# sb3.net
KiCad netlist of a schematic drawn in EAGLE
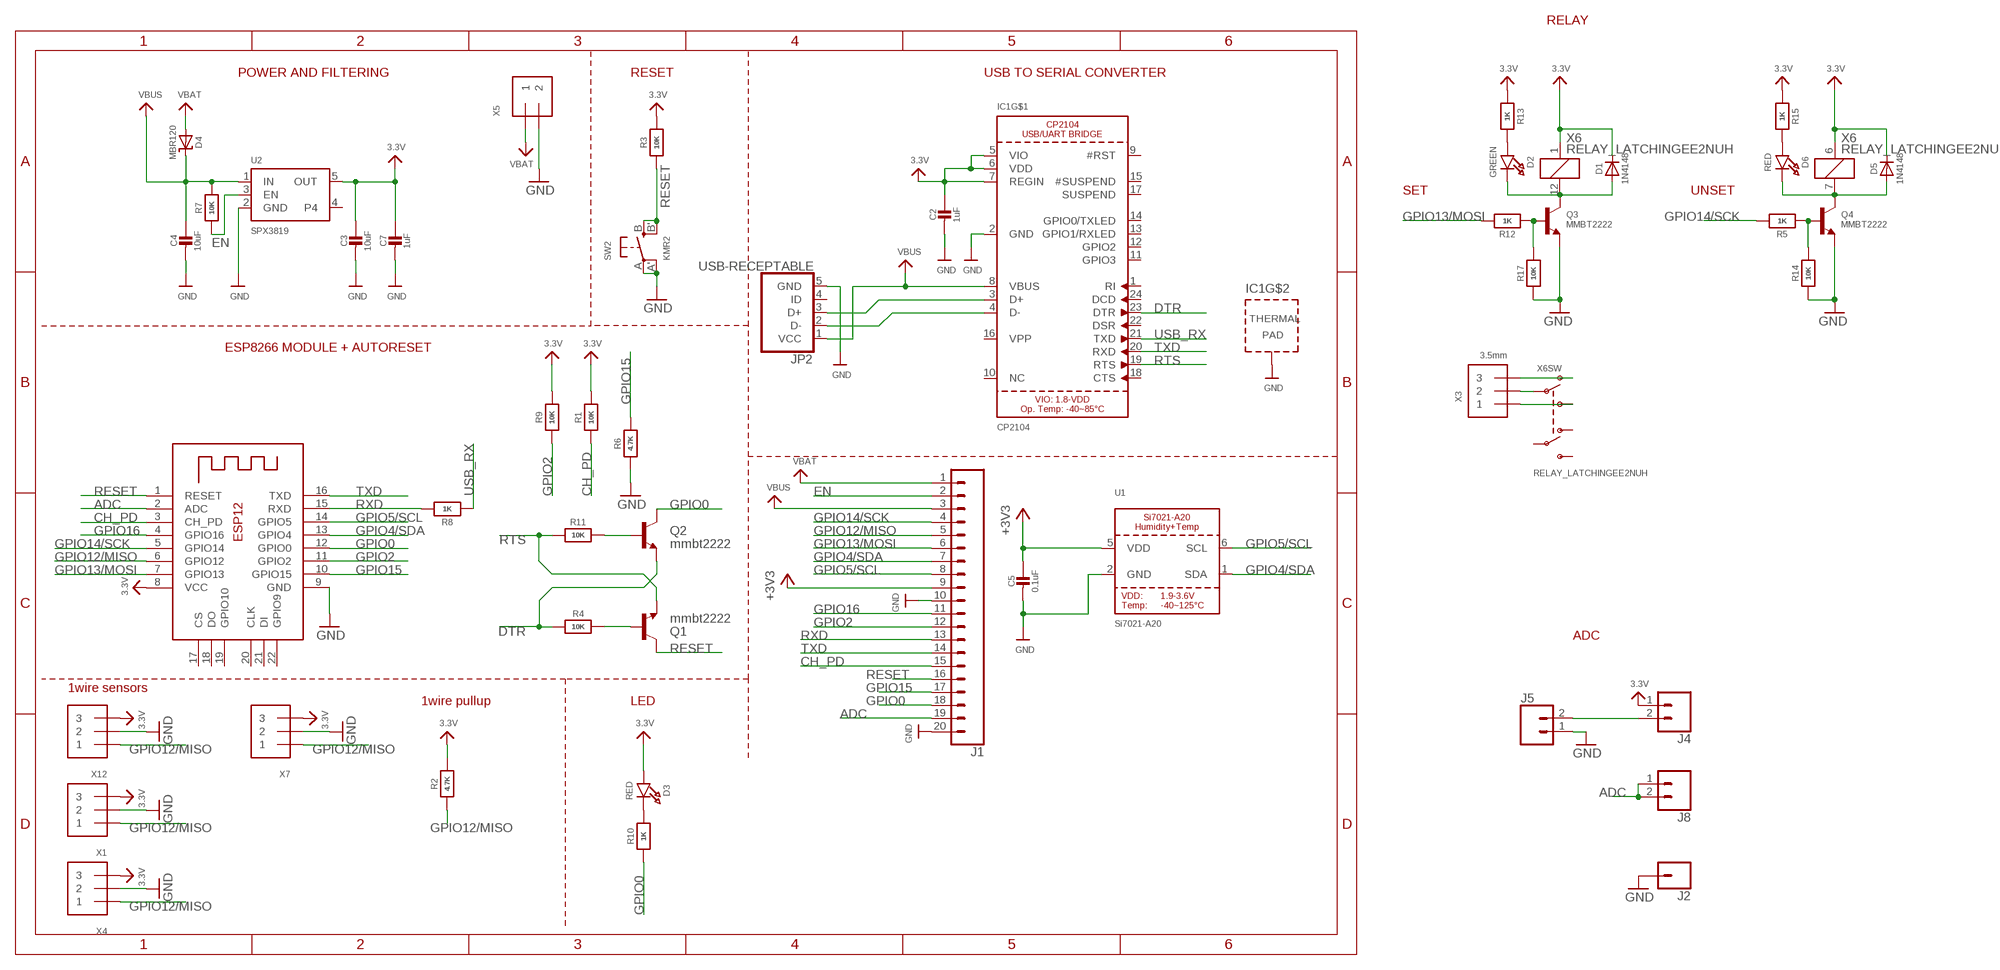
[diagram p0: schematic, sheet 1]

(export (version "E")
  (design (tool "Eeschema 10.0.6"))
  (components
    (comp (ref "C2")
      (value "1uF")
      (footprint "eagle-import:0603-NO")
      (libsource (lib "eagle-import") (part "CAP_CERAMIC0603_NO"))
    )
    (comp (ref "C3")
      (value "10uF")
      (footprint "eagle-import:0603-NO")
      (libsource (lib "eagle-import") (part "CAP_CERAMIC0603_NO"))
    )
    (comp (ref "C4")
      (value "10uF")
      (footprint "eagle-import:0603-NO")
      (libsource (lib "eagle-import") (part "CAP_CERAMIC0603_NO"))
    )
    (comp (ref "C5")
      (value "0.1uF")
      (footprint "eagle-import:0603-NO")
      (libsource (lib "eagle-import") (part "CAP_CERAMIC0603_NO"))
    )
    (comp (ref "C7")
      (value "1uF")
      (footprint "eagle-import:0603-NO")
      (libsource (lib "eagle-import") (part "CAP_CERAMIC0603_NO"))
    )
    (comp (ref "D1")
      (value "1N4148")
      (footprint "eagle-import:SOD-323")
      (libsource (lib "eagle-import") (part "DIODESOD-323"))
    )
    (comp (ref "D2")
      (value "GREEN")
      (footprint "eagle-import:CHIPLED_0805_NOOUTLINE")
      (libsource (lib "eagle-import") (part "LED0805_NOOUTLINE"))
    )
    (comp (ref "D3")
      (value "RED")
      (footprint "eagle-import:CHIPLED_0805_NOOUTLINE")
      (libsource (lib "eagle-import") (part "LED0805_NOOUTLINE"))
    )
    (comp (ref "D4")
      (value "MBR120")
      (footprint "eagle-import:SOD-123")
      (libsource (lib "eagle-import") (part "DIODE-SCHOTTKYSOD-123"))
    )
    (comp (ref "D5")
      (value "1N4148")
      (footprint "eagle-import:SOD-323")
      (libsource (lib "eagle-import") (part "DIODESOD-323"))
    )
    (comp (ref "D6")
      (value "RED")
      (footprint "eagle-import:CHIPLED_0805_NOOUTLINE")
      (libsource (lib "eagle-import") (part "LED0805_NOOUTLINE"))
    )
    (comp (ref "IC1")
      (value "CP2104")
      (footprint "eagle-import:QFN24_4MM_SMSC")
      (libsource (lib "eagle-import") (part "CP2104"))
    )
    (comp (ref "J1")
      (value "CONN_20")
      (footprint "eagle-import:1X20")
      (libsource (lib "eagle-import") (part "CONN_20"))
    )
    (comp (ref "J2")
      (value "CONN_01")
      (footprint "eagle-import:1X01")
      (libsource (lib "eagle-import") (part "CONN_01"))
    )
    (comp (ref "J4")
      (value "CONN_02")
      (footprint "eagle-import:1X02")
      (libsource (lib "eagle-import") (part "CONN_02"))
    )
    (comp (ref "J5")
      (value "CONN_023.5MM")
      (footprint "eagle-import:SCREWTERMINAL-3.5MM-2")
      (libsource (lib "eagle-import") (part "CONN_023.5MM"))
    )
    (comp (ref "J8")
      (value "CONN_02")
      (footprint "eagle-import:1X02")
      (libsource (lib "eagle-import") (part "CONN_02"))
    )
    (comp (ref "JP2")
      (value "USB-RECEPTABLE")
      (footprint "eagle-import:FCI-10103594-0001LF")
      (libsource (lib "eagle-import") (part "USB-RECEPTABLE"))
    )
    (comp (ref "Q1")
      (value "mmbt2222")
      (footprint "eagle-import:SOT23-3")
      (libsource (lib "eagle-import") (part "TRANSISTOR_NPNSOT23-3"))
    )
    (comp (ref "Q2")
      (value "mmbt2222")
      (footprint "eagle-import:SOT23-3")
      (libsource (lib "eagle-import") (part "TRANSISTOR_NPNSOT23-3"))
    )
    (comp (ref "Q3")
      (value "MMBT2222")
      (footprint "eagle-import:SOT23-R")
      (libsource (lib "eagle-import") (part "TRANSISTOR_NPN"))
    )
    (comp (ref "Q4")
      (value "MMBT2222")
      (footprint "eagle-import:SOT23-R")
      (libsource (lib "eagle-import") (part "TRANSISTOR_NPN"))
    )
    (comp (ref "R1")
      (value "10K")
      (footprint "eagle-import:0603-NO")
      (libsource (lib "eagle-import") (part "RESISTOR_0603_NOOUT"))
    )
    (comp (ref "R2")
      (value "4.7K")
      (footprint "eagle-import:0603-NO")
      (libsource (lib "eagle-import") (part "RESISTOR_0603_NOOUT"))
    )
    (comp (ref "R3")
      (value "10K")
      (footprint "eagle-import:0603-NO")
      (libsource (lib "eagle-import") (part "RESISTOR_0603_NOOUT"))
    )
    (comp (ref "R4")
      (value "10K")
      (footprint "eagle-import:0603-NO")
      (libsource (lib "eagle-import") (part "RESISTOR_0603_NOOUT"))
    )
    (comp (ref "R5")
      (value "1K")
      (footprint "eagle-import:0603-NO")
      (libsource (lib "eagle-import") (part "RESISTOR_0603_NOOUT"))
    )
    (comp (ref "R6")
      (value "4.7K")
      (footprint "eagle-import:0603-NO")
      (libsource (lib "eagle-import") (part "RESISTOR_0603_NOOUT"))
    )
    (comp (ref "R7")
      (value "10K")
      (footprint "eagle-import:0603-NO")
      (libsource (lib "eagle-import") (part "RESISTOR_0603_NOOUT"))
    )
    (comp (ref "R8")
      (value "1K")
      (footprint "eagle-import:0603-NO")
      (libsource (lib "eagle-import") (part "RESISTOR_0603_NOOUT"))
    )
    (comp (ref "R9")
      (value "10K")
      (footprint "eagle-import:0603-NO")
      (libsource (lib "eagle-import") (part "RESISTOR_0603_NOOUT"))
    )
    (comp (ref "R10")
      (value "1K")
      (footprint "eagle-import:0603-NO")
      (libsource (lib "eagle-import") (part "RESISTOR_0603_NOOUT"))
    )
    (comp (ref "R11")
      (value "10K")
      (footprint "eagle-import:0603-NO")
      (libsource (lib "eagle-import") (part "RESISTOR_0603_NOOUT"))
    )
    (comp (ref "R12")
      (value "1K")
      (footprint "eagle-import:0603-NO")
      (libsource (lib "eagle-import") (part "RESISTOR_0603_NOOUT"))
    )
    (comp (ref "R13")
      (value "1K")
      (footprint "eagle-import:0603-NO")
      (libsource (lib "eagle-import") (part "RESISTOR_0603_NOOUT"))
    )
    (comp (ref "R14")
      (value "10K")
      (footprint "eagle-import:0603-NO")
      (libsource (lib "eagle-import") (part "RESISTOR_0603_NOOUT"))
    )
    (comp (ref "R15")
      (value "1K")
      (footprint "eagle-import:0603-NO")
      (libsource (lib "eagle-import") (part "RESISTOR_0603_NOOUT"))
    )
    (comp (ref "R17")
      (value "10K")
      (footprint "eagle-import:0603-NO")
      (libsource (lib "eagle-import") (part "RESISTOR_0603_NOOUT"))
    )
    (comp (ref "SW2")
      (value "KMR2")
      (footprint "eagle-import:BTN_KMR2_4.6X2.8")
      (libsource (lib "eagle-import") (part "SWITCH_TACT_SMT4.6X2.8"))
    )
    (comp (ref "U1")
      (value "Si7021-A20")
      (footprint "eagle-import:DFN6_3X3_SI")
      (libsource (lib "eagle-import") (part "SI7021-A20"))
    )
    (comp (ref "U2")
      (value "SPX3819")
      (footprint "eagle-import:SOT23-5")
      (libsource (lib "eagle-import") (part "VREG_SOT23-5"))
    )
    (comp (ref "X1")
      (value "TERMBLOCK_1X3")
      (footprint "eagle-import:TERMBLOCK_1X3-3.5MM")
      (libsource (lib "eagle-import") (part "TERMBLOCK_1X3"))
    )
    (comp (ref "X2")
      (value "ESP-12")
      (footprint "eagle-import:ESP-12E")
      (libsource (lib "eagle-import") (part "ESP-12E"))
    )
    (comp (ref "X3")
      (value "3.5mm")
      (footprint "eagle-import:TERMBLOCK_1X3-3.5MM")
      (libsource (lib "eagle-import") (part "TERMBLOCK_1X3"))
    )
    (comp (ref "X4")
      (value "TERMBLOCK_1X3")
      (footprint "eagle-import:TERMBLOCK_1X3-3.5MM")
      (libsource (lib "eagle-import") (part "TERMBLOCK_1X3"))
    )
    (comp (ref "X5")
      (value "TERMBLOCK_1X2")
      (footprint "eagle-import:TERMBLOCK_1X2-3.5MM")
      (libsource (lib "eagle-import") (part "TERMBLOCK_1X2"))
    )
    (comp (ref "X6")
      (value "RELAY_LATCHINGEE2NUH")
      (footprint "eagle-import:RELAY_EE2_LATCH")
      (libsource (lib "eagle-import") (part "RELAY_LATCHINGEE2NUH"))
    )
    (comp (ref "X7")
      (value "TERMBLOCK_1X3")
      (footprint "eagle-import:TERMBLOCK_1X3-3.5MM")
      (libsource (lib "eagle-import") (part "TERMBLOCK_1X3"))
    )
    (comp (ref "X12")
      (value "TERMBLOCK_1X3")
      (footprint "eagle-import:TERMBLOCK_1X3-3.5MM")
      (libsource (lib "eagle-import") (part "TERMBLOCK_1X3"))
    )
  )
  (nets
    (net (code "1") (name "+3V3") (class "Default")
      (node (ref "C5") (pin "1") (pinfunction "1_1") (pintype "passive"))
      (node (ref "J1") (pin "9") (pinfunction "9_9") (pintype "passive"))
      (node (ref "U1") (pin "5") (pinfunction "VDD_5") (pintype "power_in"))
    )
    (net (code "2") (name "/ADC") (class "Default")
      (node (ref "J1") (pin "19") (pinfunction "19_19") (pintype "passive"))
      (node (ref "J8") (pin "1") (pinfunction "1_1") (pintype "passive"))
      (node (ref "J8") (pin "2") (pinfunction "2_2") (pintype "passive"))
      (node (ref "X2") (pin "2") (pinfunction "ADC_2") (pintype "passive"))
    )
    (net (code "3") (name "/CH_PD") (class "Default")
      (node (ref "J1") (pin "15") (pinfunction "15_15") (pintype "passive"))
      (node (ref "R1") (pin "1") (pinfunction "1_1") (pintype "passive"))
      (node (ref "X2") (pin "3") (pinfunction "CH_PD_3") (pintype "input"))
    )
    (net (code "4") (name "/DTR") (class "Default")
      (node (ref "IC1") (pin "23") (pinfunction "DTR_23") (pintype "output"))
      (node (ref "Q2") (pin "2") (pinfunction "E_2") (pintype "passive"))
      (node (ref "R4") (pin "1") (pinfunction "1_1") (pintype "passive"))
    )
    (net (code "5") (name "/EN") (class "Default")
      (node (ref "J1") (pin "2") (pinfunction "2_2") (pintype "passive"))
      (node (ref "R7") (pin "1") (pinfunction "1_1") (pintype "passive"))
      (node (ref "U2") (pin "3") (pinfunction "EN_3") (pintype "input"))
    )
    (net (code "6") (name "/GPIO0") (class "Default")
      (node (ref "J1") (pin "18") (pinfunction "18_18") (pintype "passive"))
      (node (ref "Q2") (pin "3") (pinfunction "C_3") (pintype "passive"))
      (node (ref "R10") (pin "1") (pinfunction "1_1") (pintype "passive"))
      (node (ref "X2") (pin "12") (pinfunction "GPIO0_12") (pintype "bidirectional"))
    )
    (net (code "7") (name "/GPIO2") (class "Default")
      (node (ref "J1") (pin "12") (pinfunction "12_12") (pintype "passive"))
      (node (ref "R9") (pin "1") (pinfunction "1_1") (pintype "passive"))
      (node (ref "X2") (pin "11") (pinfunction "GPIO2_11") (pintype "bidirectional"))
    )
    (net (code "8") (name "/GPIO4{slash}SDA") (class "Default")
      (node (ref "J1") (pin "7") (pinfunction "7_7") (pintype "passive"))
      (node (ref "U1") (pin "1") (pinfunction "SDA_1") (pintype "open_collector"))
      (node (ref "X2") (pin "13") (pinfunction "GPIO4_13") (pintype "bidirectional"))
    )
    (net (code "9") (name "/GPIO5{slash}SCL") (class "Default")
      (node (ref "J1") (pin "8") (pinfunction "8_8") (pintype "passive"))
      (node (ref "U1") (pin "6") (pinfunction "SCL_6") (pintype "open_collector"))
      (node (ref "X2") (pin "14") (pinfunction "GPIO5_14") (pintype "bidirectional"))
    )
    (net (code "10") (name "/GPIO12{slash}MISO") (class "Default")
      (node (ref "J1") (pin "5") (pinfunction "5_5") (pintype "passive"))
      (node (ref "R2") (pin "1") (pinfunction "1_1") (pintype "passive"))
      (node (ref "X1") (pin "1") (pinfunction "1_1") (pintype "passive"))
      (node (ref "X12") (pin "1") (pinfunction "1_1") (pintype "passive"))
      (node (ref "X2") (pin "6") (pinfunction "GPIO12_6") (pintype "bidirectional"))
      (node (ref "X4") (pin "1") (pinfunction "1_1") (pintype "passive"))
      (node (ref "X7") (pin "1") (pinfunction "1_1") (pintype "passive"))
    )
    (net (code "11") (name "/GPIO13{slash}MOSI") (class "Default")
      (node (ref "J1") (pin "6") (pinfunction "6_6") (pintype "passive"))
      (node (ref "R12") (pin "2") (pinfunction "2_2") (pintype "passive"))
      (node (ref "X2") (pin "7") (pinfunction "GPIO13_7") (pintype "bidirectional"))
    )
    (net (code "12") (name "/GPIO14{slash}SCK") (class "Default")
      (node (ref "J1") (pin "4") (pinfunction "4_4") (pintype "passive"))
      (node (ref "R5") (pin "2") (pinfunction "2_2") (pintype "passive"))
      (node (ref "X2") (pin "5") (pinfunction "GPIO14_5") (pintype "bidirectional"))
    )
    (net (code "13") (name "/GPIO15") (class "Default")
      (node (ref "J1") (pin "17") (pinfunction "17_17") (pintype "passive"))
      (node (ref "R6") (pin "2") (pinfunction "2_2") (pintype "passive"))
      (node (ref "X2") (pin "10") (pinfunction "GPIO15_10") (pintype "bidirectional"))
    )
    (net (code "14") (name "/GPIO16") (class "Default")
      (node (ref "J1") (pin "11") (pinfunction "11_11") (pintype "passive"))
      (node (ref "X2") (pin "4") (pinfunction "GPIO16_4") (pintype "bidirectional"))
    )
    (net (code "15") (name "/RESET") (class "Default")
      (node (ref "J1") (pin "16") (pinfunction "16_16") (pintype "passive"))
      (node (ref "Q1") (pin "3") (pinfunction "C_3") (pintype "passive"))
      (node (ref "R3") (pin "1") (pinfunction "1_1") (pintype "passive"))
      (node (ref "SW2") (pin "B") (pinfunction "S_B") (pintype "passive"))
      (node (ref "SW2") (pin "B'") (pinfunction "S1_B'") (pintype "passive"))
      (node (ref "X2") (pin "1") (pinfunction "RESET_1") (pintype "input"))
    )
    (net (code "16") (name "/RTS") (class "Default")
      (node (ref "IC1") (pin "19") (pinfunction "RTS_19") (pintype "output"))
      (node (ref "Q1") (pin "2") (pinfunction "E_2") (pintype "passive"))
      (node (ref "R11") (pin "1") (pinfunction "1_1") (pintype "passive"))
    )
    (net (code "17") (name "/RXD") (class "Default")
      (node (ref "J1") (pin "13") (pinfunction "13_13") (pintype "passive"))
      (node (ref "R8") (pin "2") (pinfunction "2_2") (pintype "passive"))
      (node (ref "X2") (pin "15") (pinfunction "RXD_15") (pintype "input"))
    )
    (net (code "18") (name "/TXD") (class "Default")
      (node (ref "IC1") (pin "20") (pinfunction "RXD_20") (pintype "input"))
      (node (ref "J1") (pin "14") (pinfunction "14_14") (pintype "passive"))
      (node (ref "X2") (pin "16") (pinfunction "TXD_16") (pintype "output"))
    )
    (net (code "19") (name "/USB_RX") (class "Default")
      (node (ref "IC1") (pin "21") (pinfunction "TXD_21") (pintype "output"))
      (node (ref "R8") (pin "1") (pinfunction "1_1") (pintype "passive"))
    )
    (net (code "20") (name "3.3V") (class "Default")
      (node (ref "C2") (pin "1") (pinfunction "1_1") (pintype "passive"))
      (node (ref "C3") (pin "1") (pinfunction "1_1") (pintype "passive"))
      (node (ref "C7") (pin "1") (pinfunction "1_1") (pintype "passive"))
      (node (ref "D1") (pin "C") (pinfunction "C_C") (pintype "passive"))
      (node (ref "D3") (pin "A") (pinfunction "A_A") (pintype "passive"))
      (node (ref "D5") (pin "C") (pinfunction "C_C") (pintype "passive"))
      (node (ref "IC1") (pin "5") (pinfunction "VIO_5") (pintype "power_in"))
      (node (ref "IC1") (pin "6") (pinfunction "VDD_6") (pintype "power_in"))
      (node (ref "IC1") (pin "7") (pinfunction "REGIN_7") (pintype "power_in"))
      (node (ref "J4") (pin "1") (pinfunction "1_1") (pintype "passive"))
      (node (ref "R1") (pin "2") (pinfunction "2_2") (pintype "passive"))
      (node (ref "R13") (pin "1") (pinfunction "1_1") (pintype "passive"))
      (node (ref "R15") (pin "1") (pinfunction "1_1") (pintype "passive"))
      (node (ref "R2") (pin "2") (pinfunction "2_2") (pintype "passive"))
      (node (ref "R3") (pin "2") (pinfunction "2_2") (pintype "passive"))
      (node (ref "R9") (pin "2") (pinfunction "2_2") (pintype "passive"))
      (node (ref "U2") (pin "5") (pinfunction "OUT_5") (pintype "power_in"))
      (node (ref "X1") (pin "3") (pinfunction "3_3") (pintype "passive"))
      (node (ref "X12") (pin "3") (pinfunction "3_3") (pintype "passive"))
      (node (ref "X2") (pin "8") (pinfunction "VCC_8") (pintype "power_in"))
      (node (ref "X4") (pin "3") (pinfunction "3_3") (pintype "passive"))
      (node (ref "X6") (pin "1") (pinfunction "1_1") (pintype "passive"))
      (node (ref "X6") (pin "6") (pinfunction "1_6") (pintype "passive"))
      (node (ref "X7") (pin "3") (pinfunction "3_3") (pintype "passive"))
    )
    (net (code "21") (name "GND") (class "Default")
      (node (ref "C2") (pin "2") (pinfunction "2_2") (pintype "passive"))
      (node (ref "C3") (pin "2") (pinfunction "2_2") (pintype "passive"))
      (node (ref "C4") (pin "2") (pinfunction "2_2") (pintype "passive"))
      (node (ref "C5") (pin "2") (pinfunction "2_2") (pintype "passive"))
      (node (ref "C7") (pin "2") (pinfunction "2_2") (pintype "passive"))
      (node (ref "IC1") (pin "2") (pinfunction "GND_2") (pintype "power_in"))
      (node (ref "IC1") (pin "THERM") (pinfunction "TP_THERM") (pintype "power_in"))
      (node (ref "J1") (pin "10") (pinfunction "10_10") (pintype "passive"))
      (node (ref "J1") (pin "20") (pinfunction "20_20") (pintype "passive"))
      (node (ref "J2") (pin "1") (pinfunction "1_1") (pintype "passive"))
      (node (ref "J5") (pin "1") (pinfunction "1_1") (pintype "passive"))
      (node (ref "JP2") (pin "5") (pinfunction "GND_5") (pintype "bidirectional"))
      (node (ref "Q3") (pin "2") (pinfunction "E_2") (pintype "passive"))
      (node (ref "Q4") (pin "2") (pinfunction "E_2") (pintype "passive"))
      (node (ref "R14") (pin "1") (pinfunction "1_1") (pintype "passive"))
      (node (ref "R17") (pin "1") (pinfunction "1_1") (pintype "passive"))
      (node (ref "R6") (pin "1") (pinfunction "1_1") (pintype "passive"))
      (node (ref "SW2") (pin "A") (pinfunction "P_A") (pintype "passive"))
      (node (ref "SW2") (pin "A'") (pinfunction "P1_A'") (pintype "passive"))
      (node (ref "U1") (pin "2") (pinfunction "GND_2") (pintype "power_in"))
      (node (ref "U2") (pin "2") (pinfunction "GND_2") (pintype "power_in"))
      (node (ref "X1") (pin "2") (pinfunction "2_2") (pintype "passive"))
      (node (ref "X12") (pin "2") (pinfunction "2_2") (pintype "passive"))
      (node (ref "X2") (pin "9") (pinfunction "GND_9") (pintype "power_in"))
      (node (ref "X4") (pin "2") (pinfunction "2_2") (pintype "passive"))
      (node (ref "X5") (pin "2") (pinfunction "2_2") (pintype "passive"))
      (node (ref "X7") (pin "2") (pinfunction "2_2") (pintype "passive"))
    )
    (net (code "22") (name "Net-(D2-PadA)") (class "Default")
      (node (ref "D2") (pin "A") (pinfunction "A_A") (pintype "passive"))
      (node (ref "R13") (pin "2") (pinfunction "2_2") (pintype "passive"))
    )
    (net (code "23") (name "Net-(D3-PadC)") (class "Default")
      (node (ref "D3") (pin "C") (pinfunction "C_C") (pintype "passive"))
      (node (ref "R10") (pin "2") (pinfunction "2_2") (pintype "passive"))
    )
    (net (code "24") (name "Net-(D6-PadA)") (class "Default")
      (node (ref "D6") (pin "A") (pinfunction "A_A") (pintype "passive"))
      (node (ref "R15") (pin "2") (pinfunction "2_2") (pintype "passive"))
    )
    (net (code "25") (name "Net-(IC1A-D+)") (class "Default")
      (node (ref "IC1") (pin "3") (pinfunction "D+_3") (pintype "bidirectional"))
      (node (ref "JP2") (pin "3") (pinfunction "D+_3") (pintype "bidirectional"))
    )
    (net (code "26") (name "Net-(IC1A-D-)") (class "Default")
      (node (ref "IC1") (pin "4") (pinfunction "D-_4") (pintype "bidirectional"))
      (node (ref "JP2") (pin "2") (pinfunction "D-_2") (pintype "bidirectional"))
    )
    (net (code "27") (name "Net-(J4-Pad2)") (class "Default")
      (node (ref "J4") (pin "2") (pinfunction "2_2") (pintype "passive"))
      (node (ref "J5") (pin "2") (pinfunction "2_2") (pintype "passive"))
    )
    (net (code "28") (name "Net-(Q1-B)") (class "Default")
      (node (ref "Q1") (pin "1") (pinfunction "B_1") (pintype "passive"))
      (node (ref "R4") (pin "2") (pinfunction "2_2") (pintype "passive"))
    )
    (net (code "29") (name "Net-(Q2-B)") (class "Default")
      (node (ref "Q2") (pin "1") (pinfunction "B_1") (pintype "passive"))
      (node (ref "R11") (pin "2") (pinfunction "2_2") (pintype "passive"))
    )
    (net (code "30") (name "Net-(Q3-B)") (class "Default")
      (node (ref "Q3") (pin "1") (pinfunction "B_1") (pintype "passive"))
      (node (ref "R12") (pin "1") (pinfunction "1_1") (pintype "passive"))
      (node (ref "R17") (pin "2") (pinfunction "2_2") (pintype "passive"))
    )
    (net (code "31") (name "Net-(Q3-C)") (class "Default")
      (node (ref "D1") (pin "A") (pinfunction "A_A") (pintype "passive"))
      (node (ref "D2") (pin "C") (pinfunction "C_C") (pintype "passive"))
      (node (ref "Q3") (pin "3") (pinfunction "C_3") (pintype "passive"))
      (node (ref "X6") (pin "12") (pinfunction "2_12") (pintype "passive"))
    )
    (net (code "32") (name "Net-(Q4-B)") (class "Default")
      (node (ref "Q4") (pin "1") (pinfunction "B_1") (pintype "passive"))
      (node (ref "R14") (pin "2") (pinfunction "2_2") (pintype "passive"))
      (node (ref "R5") (pin "1") (pinfunction "1_1") (pintype "passive"))
    )
    (net (code "33") (name "Net-(Q4-C)") (class "Default")
      (node (ref "D5") (pin "A") (pinfunction "A_A") (pintype "passive"))
      (node (ref "D6") (pin "C") (pinfunction "C_C") (pintype "passive"))
      (node (ref "Q4") (pin "3") (pinfunction "C_3") (pintype "passive"))
      (node (ref "X6") (pin "7") (pinfunction "2_7") (pintype "passive"))
    )
    (net (code "34") (name "Net-(X6C-O1)") (class "Default")
      (node (ref "X3") (pin "3") (pinfunction "3_3") (pintype "passive"))
      (node (ref "X6") (pin "10") (pinfunction "O1_10") (pintype "passive"))
    )
    (net (code "35") (name "Net-(X6C-P1)") (class "Default")
      (node (ref "X3") (pin "2") (pinfunction "2_2") (pintype "passive"))
      (node (ref "X6") (pin "9") (pinfunction "P1_9") (pintype "passive"))
    )
    (net (code "36") (name "Net-(X6C-S1)") (class "Default")
      (node (ref "X3") (pin "1") (pinfunction "1_1") (pintype "passive"))
      (node (ref "X6") (pin "8") (pinfunction "S1_8") (pintype "passive"))
    )
    (net (code "37") (name "VBAT") (class "Default")
      (node (ref "D4") (pin "A") (pinfunction "A_A") (pintype "passive"))
      (node (ref "J1") (pin "1") (pinfunction "1_1") (pintype "passive"))
      (node (ref "X5") (pin "1") (pinfunction "1_1") (pintype "passive"))
    )
    (net (code "38") (name "VBUS") (class "Default")
      (node (ref "C4") (pin "1") (pinfunction "1_1") (pintype "passive"))
      (node (ref "D4") (pin "C") (pinfunction "C_C") (pintype "passive"))
      (node (ref "IC1") (pin "8") (pinfunction "VBUS_8") (pintype "power_in"))
      (node (ref "J1") (pin "3") (pinfunction "3_3") (pintype "passive"))
      (node (ref "JP2") (pin "1") (pinfunction "VCC_1") (pintype "bidirectional"))
      (node (ref "R7") (pin "2") (pinfunction "2_2") (pintype "passive"))
      (node (ref "U2") (pin "1") (pinfunction "IN_1") (pintype "power_in"))
    )
    (net (code "39") (name "unconnected-(IC1A-#RST-Pad9)") (class "Default")
      (node (ref "IC1") (pin "9") (pinfunction "#RST_9") (pintype "bidirectional"))
    )
    (net (code "40") (name "unconnected-(IC1A-#SUSPEND-Pad15)") (class "Default")
      (node (ref "IC1") (pin "15") (pinfunction "#SUSPEND_15") (pintype "output"))
    )
    (net (code "41") (name "unconnected-(IC1A-CTS-Pad18)") (class "Default")
      (node (ref "IC1") (pin "18") (pinfunction "CTS_18") (pintype "input"))
    )
    (net (code "42") (name "unconnected-(IC1A-DCD-Pad24)") (class "Default")
      (node (ref "IC1") (pin "24") (pinfunction "DCD_24") (pintype "input"))
    )
    (net (code "43") (name "unconnected-(IC1A-DSR-Pad22)") (class "Default")
      (node (ref "IC1") (pin "22") (pinfunction "DSR_22") (pintype "input"))
    )
    (net (code "44") (name "unconnected-(IC1A-GPIO0{slash}TXLED-Pad14)") (class "Default")
      (node (ref "IC1") (pin "14") (pinfunction "GPIO0/TXLED_14") (pintype "bidirectional"))
    )
    (net (code "45") (name "unconnected-(IC1A-GPIO1{slash}RXLED-Pad13)") (class "Default")
      (node (ref "IC1") (pin "13") (pinfunction "GPIO1/RXLED_13") (pintype "bidirectional"))
    )
    (net (code "46") (name "unconnected-(IC1A-GPIO2-Pad12)") (class "Default")
      (node (ref "IC1") (pin "12") (pinfunction "GPIO2_12") (pintype "bidirectional"))
    )
    (net (code "47") (name "unconnected-(IC1A-GPIO3-Pad11)") (class "Default")
      (node (ref "IC1") (pin "11") (pinfunction "GPIO3_11") (pintype "bidirectional"))
    )
    (net (code "48") (name "unconnected-(IC1A-NC-Pad10)") (class "Default")
      (node (ref "IC1") (pin "10") (pinfunction "NC_10") (pintype "no_connect"))
    )
    (net (code "49") (name "unconnected-(IC1A-RI-Pad1)") (class "Default")
      (node (ref "IC1") (pin "1") (pinfunction "RI_1") (pintype "input"))
    )
    (net (code "50") (name "unconnected-(IC1A-SUSPEND-Pad17)") (class "Default")
      (node (ref "IC1") (pin "17") (pinfunction "SUSPEND_17") (pintype "output"))
    )
    (net (code "51") (name "unconnected-(IC1A-VPP-Pad16)") (class "Default")
      (node (ref "IC1") (pin "16") (pinfunction "VPP_16") (pintype "bidirectional"))
    )
    (net (code "52") (name "unconnected-(JP2-ID-Pad4)") (class "Default")
      (node (ref "JP2") (pin "4") (pinfunction "ID_4") (pintype "bidirectional"))
    )
    (net (code "53") (name "unconnected-(U2-P4-Pad4)") (class "Default")
      (node (ref "U2") (pin "4") (pinfunction "P4_4") (pintype "bidirectional"))
    )
    (net (code "54") (name "unconnected-(X2-CLK-Pad20)") (class "Default")
      (node (ref "X2") (pin "20") (pinfunction "CLK_20") (pintype "bidirectional"))
    )
    (net (code "55") (name "unconnected-(X2-CS-Pad17)") (class "Default")
      (node (ref "X2") (pin "17") (pinfunction "CS_17") (pintype "bidirectional"))
    )
    (net (code "56") (name "unconnected-(X2-DI-Pad21)") (class "Default")
      (node (ref "X2") (pin "21") (pinfunction "DI_21") (pintype "bidirectional"))
    )
    (net (code "57") (name "unconnected-(X2-DO-Pad18)") (class "Default")
      (node (ref "X2") (pin "18") (pinfunction "DO_18") (pintype "bidirectional"))
    )
    (net (code "58") (name "unconnected-(X2-GPIO9-Pad22)") (class "Default")
      (node (ref "X2") (pin "22") (pinfunction "GPIO9_22") (pintype "bidirectional"))
    )
    (net (code "59") (name "unconnected-(X2-GPIO10-Pad19)") (class "Default")
      (node (ref "X2") (pin "19") (pinfunction "GPIO10_19") (pintype "bidirectional"))
    )
    (net (code "60") (name "unconnected-(X6C-O2-Pad3)") (class "Default")
      (node (ref "X6") (pin "3") (pinfunction "O2_3") (pintype "passive"))
    )
    (net (code "61") (name "unconnected-(X6C-P2-Pad4)") (class "Default")
      (node (ref "X6") (pin "4") (pinfunction "P2_4") (pintype "passive"))
    )
    (net (code "62") (name "unconnected-(X6C-S2-Pad5)") (class "Default")
      (node (ref "X6") (pin "5") (pinfunction "S2_5") (pintype "passive"))
    )
  )
)
